# 2016_Carte_Batteries.net
KiCad netlist of a schematic drawn in Altium Designer
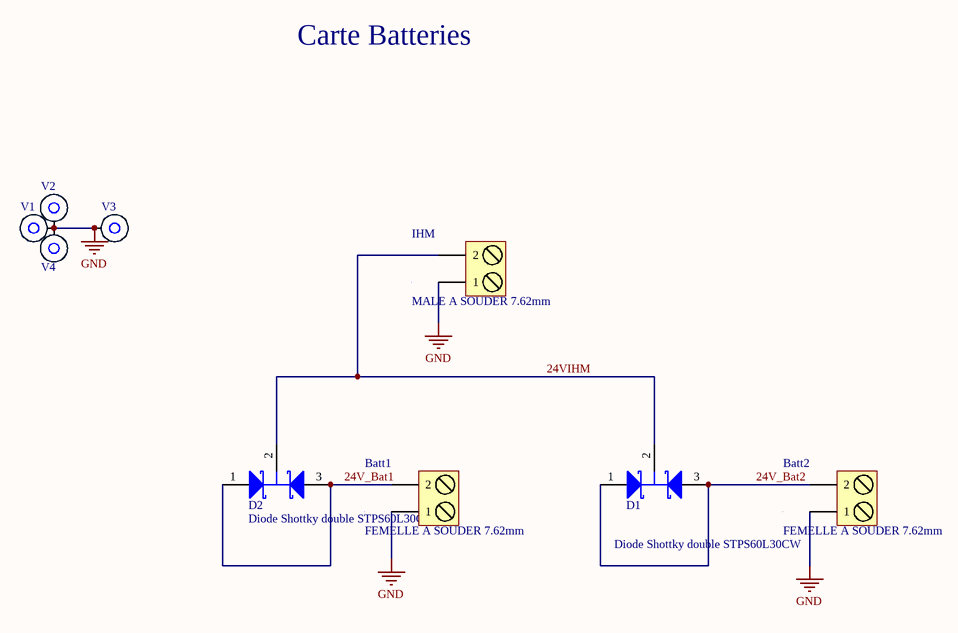
[diagram p0: 2016_Carte_Batteries.SchDoc]

(export (version "E")
  (design (tool "Eeschema 10.0.6"))
  (components
    (comp (ref "Batt1")
      (value "FEMELLE A SOUDER 7.62mm")
      (footprint "BORNIER2_FEM_COUDE")
      (description "Terminal blocks, 2 pins, pitch=5mm")
      (libsource (lib "Connecteur") (part "BORNIER2"))
    )
    (comp (ref "Batt2")
      (value "FEMELLE A SOUDER 7.62mm")
      (footprint "BORNIER2_FEM_COUDE")
      (description "Terminal blocks, 2 pins, pitch=5mm")
      (libsource (lib "Connecteur") (part "BORNIER2"))
    )
    (comp (ref "D1")
      (value "Diode Shottky double STPS60L30CW")
      (footprint "TO247")
      (description "DIODE SCHOTTKY DOUBLE")
      (fields (field (name "MANUFACTURER PART NUMBER") "BAT54C") (field (name "MANUFACTURER") "ZETEX"))
      (libsource (lib "_ROBOT") (part "Diode Shottky double STPS60L30CW"))
    )
    (comp (ref "D2")
      (value "Diode Shottky double STPS60L30CW")
      (footprint "TO247")
      (description "DIODE SCHOTTKY DOUBLE")
      (fields (field (name "MANUFACTURER PART NUMBER") "BAT54C") (field (name "MANUFACTURER") "ZETEX"))
      (libsource (lib "_ROBOT") (part "Diode Shottky double STPS60L30CW"))
    )
    (comp (ref "IHM")
      (value "MALE A SOUDER 7.62mm")
      (footprint "BORNIER2_FEM_HORIZ")
      (description "Terminal blocks, 2 pins, pitch=5mm")
      (libsource (lib "Connecteur") (part "BORNIER2"))
    )
    (comp (ref "V1")
      (value "~")
      (footprint "ENTRETOISE_CMS")
      (description "Entretoise Wurth")
      (fields (field (name "PUBLISHER") "Damien Guitton"))
      (libsource (lib "_ROBOT") (part "Entretoise WURTH CMS"))
    )
    (comp (ref "V2")
      (value "~")
      (footprint "ENTRETOISE_CMS")
      (description "Entretoise Wurth")
      (fields (field (name "PUBLISHER") "Damien Guitton"))
      (libsource (lib "_ROBOT") (part "Entretoise WURTH CMS"))
    )
    (comp (ref "V3")
      (value "~")
      (footprint "ENTRETOISE_CMS")
      (description "Entretoise Wurth")
      (fields (field (name "PUBLISHER") "Damien Guitton"))
      (libsource (lib "_ROBOT") (part "Entretoise WURTH CMS"))
    )
    (comp (ref "V4")
      (value "~")
      (footprint "ENTRETOISE_CMS")
      (description "Entretoise Wurth")
      (fields (field (name "PUBLISHER") "Damien Guitton"))
      (libsource (lib "_ROBOT") (part "Entretoise WURTH CMS"))
    )
  )
  (nets
    (net (code "1") (name "/24VIHM") (class "Default")
      (node (ref "D1") (pin "2") (pinfunction "K_2") (pintype "passive"))
      (node (ref "D2") (pin "2") (pinfunction "K_2") (pintype "passive"))
      (node (ref "IHM") (pin "2") (pinfunction "2_2") (pintype "passive"))
    )
    (net (code "2") (name "/24V_Bat1") (class "Default")
      (node (ref "Batt1") (pin "2") (pinfunction "2_2") (pintype "passive"))
      (node (ref "D2") (pin "1") (pinfunction "A1_1") (pintype "passive"))
      (node (ref "D2") (pin "3") (pinfunction "A2_3") (pintype "passive"))
    )
    (net (code "3") (name "/24V_Bat2") (class "Default")
      (node (ref "Batt2") (pin "2") (pinfunction "2_2") (pintype "passive"))
      (node (ref "D1") (pin "1") (pinfunction "A1_1") (pintype "passive"))
      (node (ref "D1") (pin "3") (pinfunction "A2_3") (pintype "passive"))
    )
    (net (code "4") (name "GND") (class "Default")
      (node (ref "Batt1") (pin "1") (pinfunction "1_1") (pintype "passive"))
      (node (ref "Batt2") (pin "1") (pinfunction "1_1") (pintype "passive"))
      (node (ref "IHM") (pin "1") (pinfunction "1_1") (pintype "passive"))
      (node (ref "V1") (pin "1") (pinfunction "1_1") (pintype "passive"))
      (node (ref "V2") (pin "1") (pinfunction "1_1") (pintype "passive"))
      (node (ref "V3") (pin "1") (pinfunction "1_1") (pintype "passive"))
      (node (ref "V4") (pin "1") (pinfunction "1_1") (pintype "passive"))
    )
  )
)
